# Top.net
KiCad netlist of a schematic drawn in Altium Designer
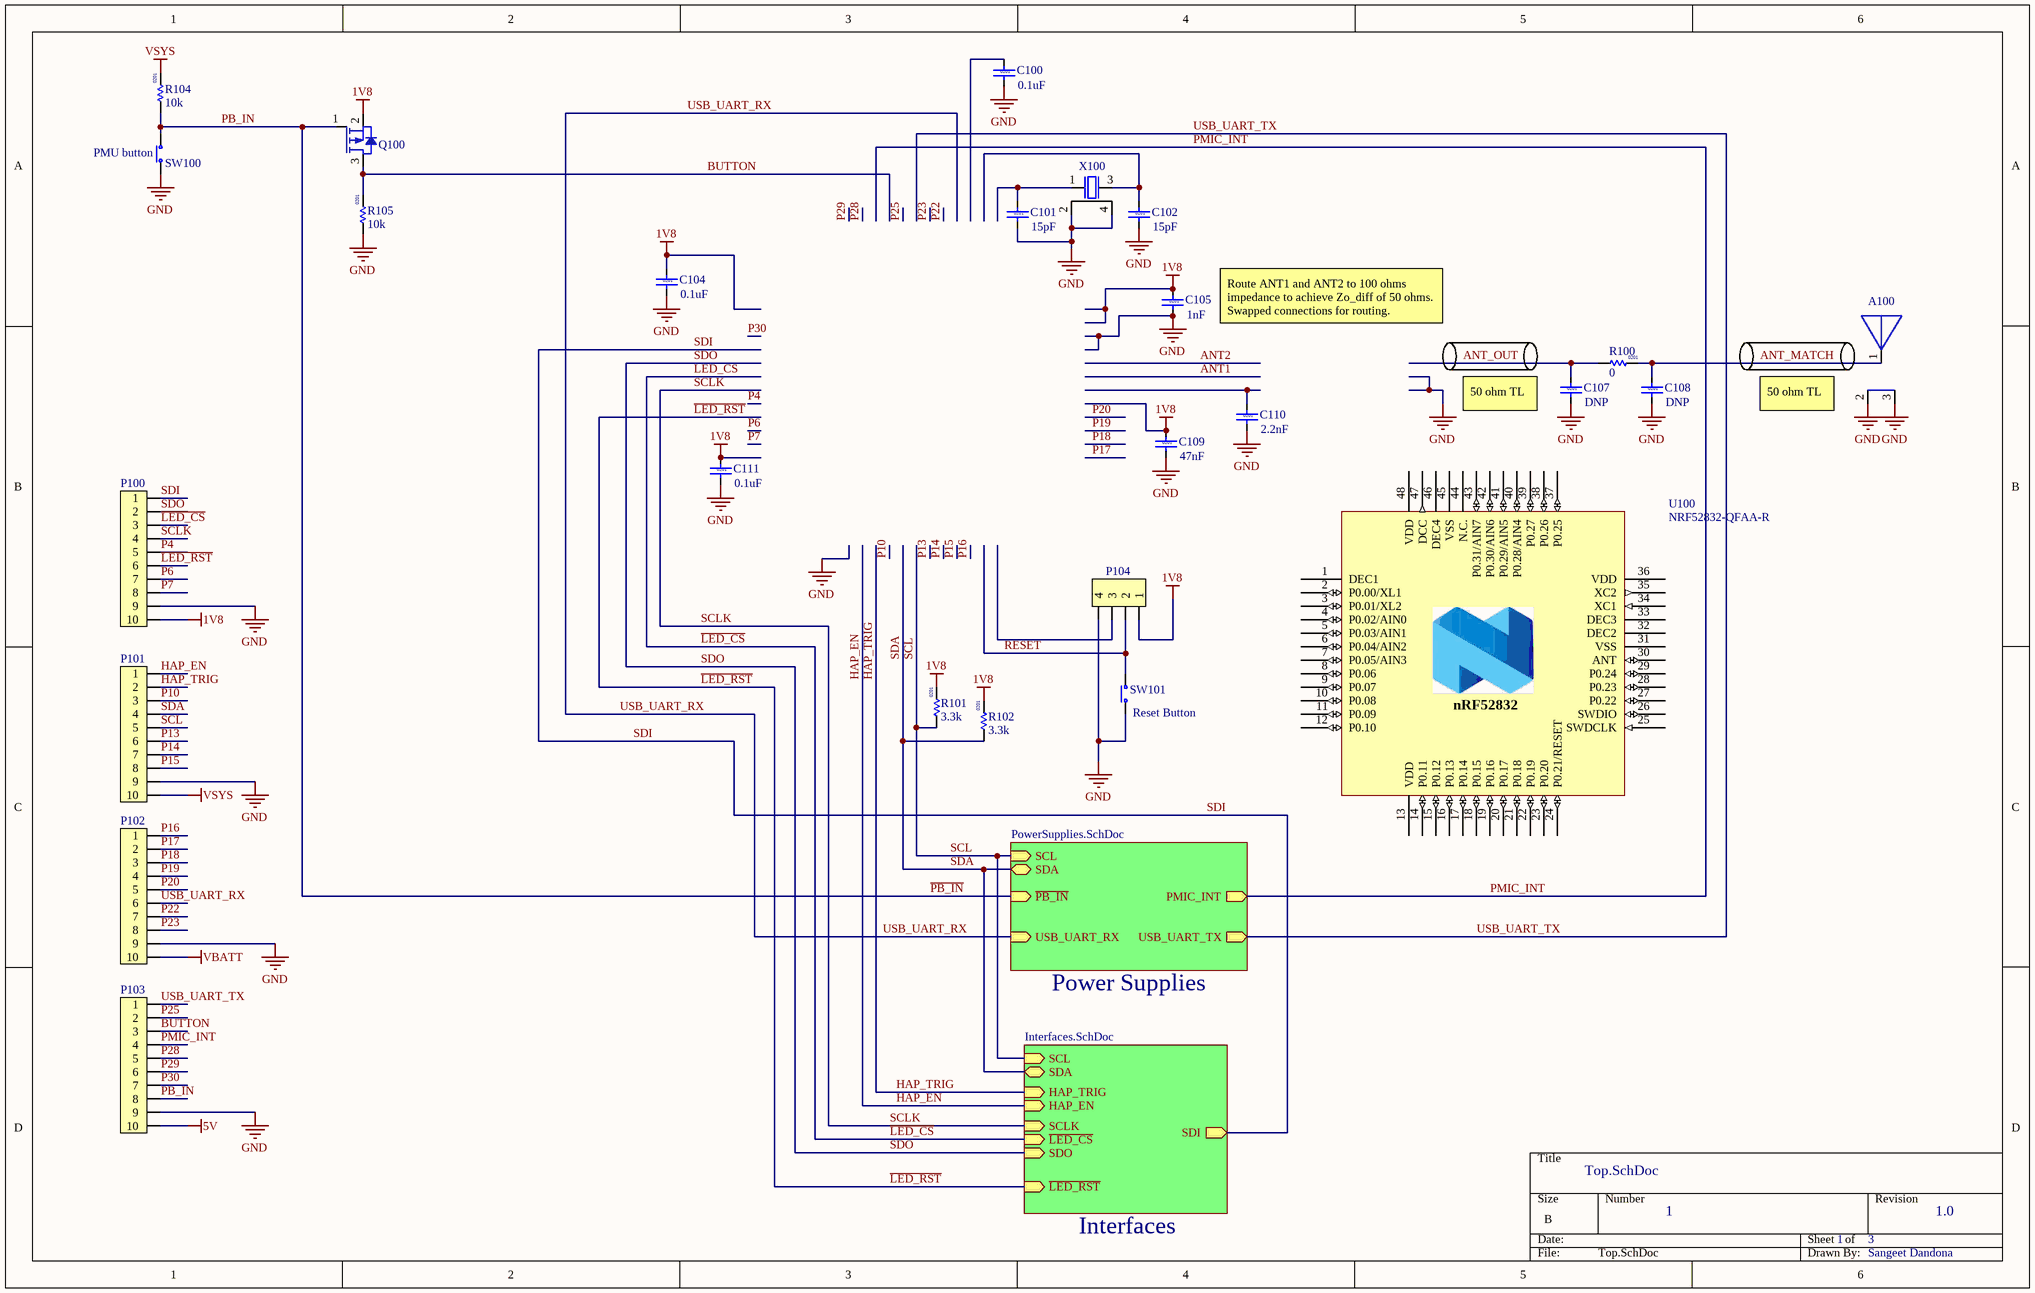
[diagram p0: Top.SchDoc]

(export (version "E")
  (design (tool "Eeschema 10.0.6"))
  (components
    (comp (ref "A100")
      (value "~")
      (footprint "2450AT07A0100")
      (description "ANTENNA SMD EIA 0402 2.4GHZ")
      (fields (field (name "MF") "Johanson Technology Inc."))
      (libsource (lib "Rigado_AltiumLib") (part "ANT_GND_4Pin"))
    )
    (comp (ref "C100")
      (value "0.1uF")
      (footprint "Cap 0201 HD")
      (description "CAP CER 0.1UF 6.3V 10% X5R 0201")
      (fields (field (name "SIZE") "0201") (field (name "MF") "Murata Electronics North America"))
      (libsource (lib "Rigado_AltiumLib") (part "Cap Chip"))
    )
    (comp (ref "C101")
      (value "15pF")
      (footprint "Cap 0201 HD")
      (description "CAP CER 15PF 25V NP0 0201")
      (fields (field (name "SIZE") "0201") (field (name "MF") "Murata Electronics North America"))
      (libsource (lib "Rigado_AltiumLib") (part "Cap Chip"))
    )
    (comp (ref "C102")
      (value "15pF")
      (footprint "Cap 0201 HD")
      (description "CAP CER 15PF 25V NP0 0201")
      (fields (field (name "SIZE") "0201") (field (name "MF") "Murata Electronics North America"))
      (libsource (lib "Rigado_AltiumLib") (part "Cap Chip"))
    )
    (comp (ref "C104")
      (value "0.1uF")
      (footprint "Cap 0201 HD")
      (description "CAP CER 0.1UF 6.3V 10% X5R 0201")
      (fields (field (name "SIZE") "0201") (field (name "MF") "Murata Electronics North America"))
      (libsource (lib "Rigado_AltiumLib") (part "Cap Chip"))
    )
    (comp (ref "C105")
      (value "1nF")
      (footprint "Cap 0201 HD")
      (description "CAP CER 1000PF 25V 10% X7R 0201")
      (fields (field (name "SIZE") "0201") (field (name "MF") "Murata Electronics North America"))
      (libsource (lib "Rigado_AltiumLib") (part "Cap Chip"))
    )
    (comp (ref "C107")
      (value "DNP")
      (footprint "Cap 0201 HD")
      (description "Capacitor, Ceramic 0201, DNP")
      (fields (field (name "SIZE") "0201"))
      (libsource (lib "Rigado_AltiumLib") (part "Cap Chip"))
    )
    (comp (ref "C108")
      (value "DNP")
      (footprint "Cap 0201 HD")
      (description "Capacitor, Ceramic 0201, DNP")
      (fields (field (name "SIZE") "0201"))
      (libsource (lib "Rigado_AltiumLib") (part "Cap Chip"))
    )
    (comp (ref "C109")
      (value "47nF")
      (footprint "Cap 0201 HD")
      (description "CAP CER 0.047UF 10V 10% X5R 0201")
      (fields (field (name "SIZE") "0201") (field (name "MF") "Taiyo Yuden"))
      (libsource (lib "Rigado_AltiumLib") (part "Cap Chip"))
    )
    (comp (ref "C110")
      (value "2.2nF")
      (footprint "Cap 0201 HD")
      (description "CAP CER 2200PF 16V 10% X7R 0201")
      (fields (field (name "SIZE") "0201") (field (name "MF") "Murata Electronics North America"))
      (libsource (lib "Rigado_AltiumLib") (part "Cap Chip"))
    )
    (comp (ref "C111")
      (value "0.1uF")
      (footprint "Cap 0201 HD")
      (description "CAP CER 0.1UF 6.3V 10% X5R 0201")
      (fields (field (name "SIZE") "0201") (field (name "MF") "Murata Electronics North America"))
      (libsource (lib "Rigado_AltiumLib") (part "Cap Chip"))
    )
    (comp (ref "P100")
      (value "~")
      (footprint "Molex 15-91-2100")
      (description "CONN HEADER 10POS .100\" VERT TIN")
      (fields (field (name "MF") "Molex, LLC"))
      (libsource (lib "JDB-001") (part "CONN-10"))
    )
    (comp (ref "P101")
      (value "~")
      (footprint "Molex 15-91-2100")
      (description "CONN HEADER 10POS .100\" VERT TIN")
      (fields (field (name "MF") "Molex, LLC"))
      (libsource (lib "JDB-001") (part "CONN-10"))
    )
    (comp (ref "P102")
      (value "~")
      (footprint "Molex 15-91-2100")
      (description "CONN HEADER 10POS .100\" VERT TIN")
      (fields (field (name "MF") "Molex, LLC"))
      (libsource (lib "JDB-001") (part "CONN-10"))
    )
    (comp (ref "P103")
      (value "~")
      (footprint "Molex 15-91-2100")
      (description "CONN HEADER 10POS .100\" VERT TIN")
      (fields (field (name "MF") "Molex, LLC"))
      (libsource (lib "JDB-001") (part "CONN-10"))
    )
    (comp (ref "P104")
      (value "~")
      (footprint "LIST_1x4_SMD")
      (description "BOARD-BOARD CONNECTOR HEADER, 4WAY, 1ROW")
      (fields (field (name "MF") "GLOBAL CONNECTOR TECHNOLOGY"))
      (libsource (lib "JDB-001") (part "CONN-4"))
    )
    (comp (ref "Q100")
      (value "~")
      (footprint "SOT-723")
      (description "MOSFET P-CH 20V 0.1A VMT3")
      (fields (field (name "MF") "Rohm Semiconductor"))
      (libsource (lib "JDB-001") (part "MOSFET-P"))
    )
    (comp (ref "R100")
      (value "0")
      (footprint "RES 0201 HD")
      (description "RES SMD 0.0OHM JUMPER 1/20W 0201")
      (fields (field (name "SIZE") "0201") (field (name "MF") "Samsung Electro-Mechanics America, Inc."))
      (libsource (lib "Rigado_AltiumLib") (part "Res sm"))
    )
    (comp (ref "R101")
      (value "3.3k")
      (footprint "RES 0201 HD")
      (description "RES SMD 3.3K OHM 5% 1/20W 0201")
      (fields (field (name "SIZE") "0201") (field (name "MF") "Samsung Electro-Mechanics America, Inc."))
      (libsource (lib "Rigado_AltiumLib") (part "Res sm"))
    )
    (comp (ref "R102")
      (value "3.3k")
      (footprint "RES 0201 HD")
      (description "RES SMD 3.3K OHM 5% 1/20W 0201")
      (fields (field (name "SIZE") "0201") (field (name "MF") "Samsung Electro-Mechanics America, Inc."))
      (libsource (lib "Rigado_AltiumLib") (part "Res sm"))
    )
    (comp (ref "R104")
      (value "10k")
      (footprint "RES 0201 HD")
      (description "RES SMD 10K OHM 5% 1/20W 0201")
      (fields (field (name "SIZE") "0201") (field (name "MF") "Rohm Semiconductor"))
      (libsource (lib "Rigado_AltiumLib") (part "Res sm"))
    )
    (comp (ref "R105")
      (value "10k")
      (footprint "RES 0201 HD")
      (description "RES SMD 10K OHM 5% 1/20W 0201")
      (fields (field (name "SIZE") "0201") (field (name "MF") "Rohm Semiconductor"))
      (libsource (lib "Rigado_AltiumLib") (part "Res sm"))
    )
    (comp (ref "SW100")
      (value "~")
      (footprint "ALPS_SKHUxxx010_WO_GND")
      (description "Tactile Switches 6.0x6.0x2.5mm 160gf")
      (fields (field (name "MF") "ALPS"))
      (libsource (lib "JDB-001") (part "SW-PB"))
    )
    (comp (ref "SW101")
      (value "~")
      (footprint "ALPS_SKHUxxx010_WO_GND")
      (description "Tactile Switches 6.0x6.0x2.5mm 160gf")
      (fields (field (name "MF") "ALPS"))
      (libsource (lib "JDB-001") (part "SW-PB"))
    )
    (comp (ref "U100")
      (value "NRF52832-QFAA-R")
      (footprint "QFN40P600X600X90-48N")
      (description "IC RF TXRX+MCU BLUETOOTH 48QFN")
      (fields (field (name "MF") "Nordic Semiconductor ASA") (field (name "MFPN") "NRF52832-QFAA-R"))
      (libsource (lib "JDB-002") (part "nRF52832_QFAA"))
    )
    (comp (ref "X100")
      (value "~")
      (footprint "XTAL_ABM11-16")
      (description "CRYSTAL 16.0000MHZ 10PF SMD")
      (fields (field (name "MF") "Abracon LLC"))
      (libsource (lib "JWB-001_Main") (part "XTAL_ABM11-16"))
    )
  )
  (nets
    (net (code "3") (name "/ANT_MATCH") (class "Default")
      (node (ref "A100") (pin "1") (pinfunction "1_1") (pintype "passive"))
      (node (ref "C108") (pin "1") (pinfunction "1_1") (pintype "passive"))
      (node (ref "R100") (pin "2") (pinfunction "2_2") (pintype "passive"))
    )
    (net (code "4") (name "/ANT_OUT") (class "Default")
      (node (ref "C107") (pin "1") (pinfunction "1_1") (pintype "passive"))
      (node (ref "R100") (pin "1") (pinfunction "1_1") (pintype "passive"))
    )
    (net (code "5") (name "/BUTTON") (class "Default")
      (node (ref "P103") (pin "3") (pinfunction "3_3") (pintype "power_in"))
      (node (ref "Q100") (pin "3") (pinfunction "D_3") (pintype "passive"))
      (node (ref "R105") (pin "2") (pinfunction "2_2") (pintype "passive"))
    )
    (net (code "6") (name "/HAP_EN") (class "Default")
      (node (ref "P101") (pin "1") (pinfunction "1_1") (pintype "power_in"))
    )
    (net (code "7") (name "/HAP_TRIG") (class "Default")
      (node (ref "P101") (pin "2") (pinfunction "2_2") (pintype "power_in"))
    )
    (net (code "8") (name "/LED_CS") (class "Default")
      (node (ref "P100") (pin "3") (pinfunction "3_3") (pintype "power_in"))
    )
    (net (code "9") (name "/LED_RST") (class "Default")
      (node (ref "P100") (pin "6") (pinfunction "6_6") (pintype "power_in"))
    )
    (net (code "10") (name "/P4") (class "Default")
      (node (ref "P100") (pin "5") (pinfunction "5_5") (pintype "power_in"))
    )
    (net (code "11") (name "/P6") (class "Default")
      (node (ref "P100") (pin "7") (pinfunction "7_7") (pintype "power_in"))
    )
    (net (code "12") (name "/P7") (class "Default")
      (node (ref "P100") (pin "8") (pinfunction "8_8") (pintype "power_in"))
    )
    (net (code "13") (name "/P10") (class "Default")
      (node (ref "P101") (pin "3") (pinfunction "3_3") (pintype "power_in"))
    )
    (net (code "14") (name "/P13") (class "Default")
      (node (ref "P101") (pin "6") (pinfunction "6_6") (pintype "power_in"))
    )
    (net (code "15") (name "/P14") (class "Default")
      (node (ref "P101") (pin "7") (pinfunction "7_7") (pintype "power_in"))
    )
    (net (code "16") (name "/P15") (class "Default")
      (node (ref "P101") (pin "8") (pinfunction "8_8") (pintype "power_in"))
    )
    (net (code "17") (name "/P16") (class "Default")
      (node (ref "P102") (pin "1") (pinfunction "1_1") (pintype "power_in"))
    )
    (net (code "18") (name "/P17") (class "Default")
      (node (ref "P102") (pin "2") (pinfunction "2_2") (pintype "power_in"))
    )
    (net (code "19") (name "/P18") (class "Default")
      (node (ref "P102") (pin "3") (pinfunction "3_3") (pintype "power_in"))
    )
    (net (code "20") (name "/P19") (class "Default")
      (node (ref "P102") (pin "4") (pinfunction "4_4") (pintype "power_in"))
    )
    (net (code "21") (name "/P20") (class "Default")
      (node (ref "P102") (pin "5") (pinfunction "5_5") (pintype "power_in"))
    )
    (net (code "22") (name "/P22") (class "Default")
      (node (ref "P102") (pin "7") (pinfunction "7_7") (pintype "power_in"))
    )
    (net (code "23") (name "/P23") (class "Default")
      (node (ref "P102") (pin "8") (pinfunction "8_8") (pintype "power_in"))
    )
    (net (code "24") (name "/P25") (class "Default")
      (node (ref "P103") (pin "2") (pinfunction "2_2") (pintype "power_in"))
    )
    (net (code "25") (name "/P28") (class "Default")
      (node (ref "P103") (pin "5") (pinfunction "5_5") (pintype "power_in"))
    )
    (net (code "26") (name "/P29") (class "Default")
      (node (ref "P103") (pin "6") (pinfunction "6_6") (pintype "power_in"))
    )
    (net (code "27") (name "/P30") (class "Default")
      (node (ref "P103") (pin "7") (pinfunction "7_7") (pintype "power_in"))
    )
    (net (code "28") (name "/PB_IN") (class "Default")
      (node (ref "P103") (pin "8") (pinfunction "8_8") (pintype "power_in"))
      (node (ref "Q100") (pin "1") (pinfunction "G_1") (pintype "passive"))
      (node (ref "R104") (pin "1") (pinfunction "1_1") (pintype "passive"))
      (node (ref "SW100") (pin "1") (pinfunction "N.O_1") (pintype "passive"))
    )
    (net (code "29") (name "/PMIC_INT") (class "Default")
      (node (ref "P103") (pin "4") (pinfunction "4_4") (pintype "power_in"))
    )
    (net (code "30") (name "/RESET") (class "Default")
      (node (ref "P104") (pin "2") (pinfunction "2_2") (pintype "passive"))
      (node (ref "SW101") (pin "1") (pinfunction "N.O_1") (pintype "passive"))
    )
    (net (code "31") (name "/SCL") (class "Default")
      (node (ref "P101") (pin "5") (pinfunction "5_5") (pintype "power_in"))
      (node (ref "R101") (pin "1") (pinfunction "1_1") (pintype "passive"))
    )
    (net (code "32") (name "/SCLK") (class "Default")
      (node (ref "P100") (pin "4") (pinfunction "4_4") (pintype "power_in"))
    )
    (net (code "33") (name "/SDA") (class "Default")
      (node (ref "P101") (pin "4") (pinfunction "4_4") (pintype "power_in"))
      (node (ref "R102") (pin "1") (pinfunction "1_1") (pintype "passive"))
    )
    (net (code "34") (name "/SDI") (class "Default")
      (node (ref "P100") (pin "1") (pinfunction "1_1") (pintype "power_in"))
    )
    (net (code "35") (name "/SDO") (class "Default")
      (node (ref "P100") (pin "2") (pinfunction "2_2") (pintype "power_in"))
    )
    (net (code "36") (name "/USB_UART_RX") (class "Default")
      (node (ref "P102") (pin "6") (pinfunction "6_6") (pintype "power_in"))
    )
    (net (code "37") (name "/USB_UART_TX") (class "Default")
      (node (ref "P103") (pin "1") (pinfunction "1_1") (pintype "power_in"))
    )
    (net (code "38") (name "1V8") (class "Default")
      (node (ref "C104") (pin "1") (pinfunction "1_1") (pintype "passive"))
      (node (ref "C105") (pin "1") (pinfunction "1_1") (pintype "passive"))
      (node (ref "C109") (pin "1") (pinfunction "1_1") (pintype "passive"))
      (node (ref "C111") (pin "1") (pinfunction "1_1") (pintype "passive"))
      (node (ref "P100") (pin "10") (pinfunction "10_10") (pintype "power_in"))
      (node (ref "P104") (pin "1") (pinfunction "1_1") (pintype "passive"))
      (node (ref "Q100") (pin "2") (pinfunction "S_2") (pintype "passive"))
      (node (ref "R101") (pin "2") (pinfunction "2_2") (pintype "passive"))
      (node (ref "R102") (pin "2") (pinfunction "2_2") (pintype "passive"))
    )
    (net (code "39") (name "5V") (class "Default")
      (node (ref "P103") (pin "10") (pinfunction "10_10") (pintype "power_in"))
    )
    (net (code "40") (name "GND") (class "Default")
      (node (ref "A100") (pin "2") (pinfunction "2_2") (pintype "power_in"))
      (node (ref "A100") (pin "3") (pinfunction "3_3") (pintype "power_in"))
      (node (ref "C100") (pin "2") (pinfunction "2_2") (pintype "passive"))
      (node (ref "C101") (pin "2") (pinfunction "2_2") (pintype "passive"))
      (node (ref "C102") (pin "2") (pinfunction "2_2") (pintype "passive"))
      (node (ref "C104") (pin "2") (pinfunction "2_2") (pintype "passive"))
      (node (ref "C105") (pin "2") (pinfunction "2_2") (pintype "passive"))
      (node (ref "C107") (pin "2") (pinfunction "2_2") (pintype "passive"))
      (node (ref "C108") (pin "2") (pinfunction "2_2") (pintype "passive"))
      (node (ref "C109") (pin "2") (pinfunction "2_2") (pintype "passive"))
      (node (ref "C110") (pin "2") (pinfunction "2_2") (pintype "passive"))
      (node (ref "C111") (pin "2") (pinfunction "2_2") (pintype "passive"))
      (node (ref "P100") (pin "9") (pinfunction "9_9") (pintype "power_in"))
      (node (ref "P101") (pin "9") (pinfunction "9_9") (pintype "power_in"))
      (node (ref "P102") (pin "9") (pinfunction "9_9") (pintype "power_in"))
      (node (ref "P103") (pin "9") (pinfunction "9_9") (pintype "power_in"))
      (node (ref "P104") (pin "4") (pinfunction "4_4") (pintype "power_in"))
      (node (ref "R105") (pin "1") (pinfunction "1_1") (pintype "passive"))
      (node (ref "SW100") (pin "2") (pinfunction "COM_2") (pintype "passive"))
      (node (ref "SW101") (pin "2") (pinfunction "COM_2") (pintype "passive"))
      (node (ref "U100") (pin "49") (pinfunction "GND_49") (pintype "power_in"))
      (node (ref "X100") (pin "2") (pintype "passive"))
      (node (ref "X100") (pin "4") (pintype "passive"))
    )
    (net (code "41") (name "Net-(C101-Pad1)") (class "Default")
      (node (ref "C101") (pin "1") (pinfunction "1_1") (pintype "passive"))
      (node (ref "X100") (pin "1") (pintype "passive"))
    )
    (net (code "42") (name "Net-(C102-Pad1)") (class "Default")
      (node (ref "C102") (pin "1") (pinfunction "1_1") (pintype "passive"))
      (node (ref "X100") (pin "3") (pintype "passive"))
    )
    (net (code "43") (name "VBATT") (class "Default")
      (node (ref "P102") (pin "10") (pinfunction "10_10") (pintype "power_in"))
    )
    (net (code "44") (name "VSYS") (class "Default")
      (node (ref "P101") (pin "10") (pinfunction "10_10") (pintype "power_in"))
      (node (ref "R104") (pin "2") (pinfunction "2_2") (pintype "passive"))
    )
    (net (code "45") (name "unconnected-(C100-Pad1)") (class "Default")
      (node (ref "C100") (pin "1") (pinfunction "1_1") (pintype "passive"))
    )
    (net (code "46") (name "unconnected-(C110-Pad1)") (class "Default")
      (node (ref "C110") (pin "1") (pinfunction "1_1") (pintype "passive"))
    )
    (net (code "47") (name "unconnected-(P104-Pad3)") (class "Default")
      (node (ref "P104") (pin "3") (pinfunction "3_3") (pintype "power_in"))
    )
    (net (code "48") (name "unconnected-(U100-ANT-Pad30)") (class "Default")
      (node (ref "U100") (pin "30") (pinfunction "ANT_30") (pintype "bidirectional"))
    )
    (net (code "49") (name "unconnected-(U100-DCC-Pad47)") (class "Default")
      (node (ref "U100") (pin "47") (pinfunction "DCC_47") (pintype "output"))
    )
    (net (code "50") (name "unconnected-(U100-DEC1-Pad1)") (class "Default")
      (node (ref "U100") (pin "1") (pinfunction "DEC1_1") (pintype "power_in"))
    )
    (net (code "51") (name "unconnected-(U100-DEC2-Pad32)") (class "Default")
      (node (ref "U100") (pin "32") (pinfunction "DEC2_32") (pintype "power_in"))
    )
    (net (code "52") (name "unconnected-(U100-DEC3-Pad33)") (class "Default")
      (node (ref "U100") (pin "33") (pinfunction "DEC3_33") (pintype "power_in"))
    )
    (net (code "53") (name "unconnected-(U100-DEC4-Pad46)") (class "Default")
      (node (ref "U100") (pin "46") (pinfunction "DEC4_46") (pintype "power_in"))
    )
    (net (code "54") (name "unconnected-(U100-N.C.-Pad44)") (class "Default")
      (node (ref "U100") (pin "44") (pinfunction "N.C._44") (pintype "power_in"))
    )
    (net (code "55") (name "unconnected-(U100-P0.00{slash}XL1-Pad2)") (class "Default")
      (node (ref "U100") (pin "2") (pinfunction "P0.00/XL1_2") (pintype "bidirectional"))
    )
    (net (code "56") (name "unconnected-(U100-P0.01{slash}XL2-Pad3)") (class "Default")
      (node (ref "U100") (pin "3") (pinfunction "P0.01/XL2_3") (pintype "bidirectional"))
    )
    (net (code "57") (name "unconnected-(U100-P0.02{slash}AIN0-Pad4)") (class "Default")
      (node (ref "U100") (pin "4") (pinfunction "P0.02/AIN0_4") (pintype "bidirectional"))
    )
    (net (code "58") (name "unconnected-(U100-P0.03{slash}AIN1-Pad5)") (class "Default")
      (node (ref "U100") (pin "5") (pinfunction "P0.03/AIN1_5") (pintype "bidirectional"))
    )
    (net (code "59") (name "unconnected-(U100-P0.04{slash}AIN2-Pad6)") (class "Default")
      (node (ref "U100") (pin "6") (pinfunction "P0.04/AIN2_6") (pintype "bidirectional"))
    )
    (net (code "60") (name "unconnected-(U100-P0.05{slash}AIN3-Pad7)") (class "Default")
      (node (ref "U100") (pin "7") (pinfunction "P0.05/AIN3_7") (pintype "bidirectional"))
    )
    (net (code "61") (name "unconnected-(U100-P0.06-Pad8)") (class "Default")
      (node (ref "U100") (pin "8") (pinfunction "P0.06_8") (pintype "bidirectional"))
    )
    (net (code "62") (name "unconnected-(U100-P0.07-Pad9)") (class "Default")
      (node (ref "U100") (pin "9") (pinfunction "P0.07_9") (pintype "bidirectional"))
    )
    (net (code "63") (name "unconnected-(U100-P0.08-Pad10)") (class "Default")
      (node (ref "U100") (pin "10") (pinfunction "P0.08_10") (pintype "bidirectional"))
    )
    (net (code "64") (name "unconnected-(U100-P0.09-Pad11)") (class "Default")
      (node (ref "U100") (pin "11") (pinfunction "P0.09_11") (pintype "bidirectional"))
    )
    (net (code "65") (name "unconnected-(U100-P0.10-Pad12)") (class "Default")
      (node (ref "U100") (pin "12") (pinfunction "P0.10_12") (pintype "bidirectional"))
    )
    (net (code "66") (name "unconnected-(U100-P0.11-Pad14)") (class "Default")
      (node (ref "U100") (pin "14") (pinfunction "P0.11_14") (pintype "bidirectional"))
    )
    (net (code "67") (name "unconnected-(U100-P0.12-Pad15)") (class "Default")
      (node (ref "U100") (pin "15") (pinfunction "P0.12_15") (pintype "bidirectional"))
    )
    (net (code "68") (name "unconnected-(U100-P0.13-Pad16)") (class "Default")
      (node (ref "U100") (pin "16") (pinfunction "P0.13_16") (pintype "bidirectional"))
    )
    (net (code "69") (name "unconnected-(U100-P0.14-Pad17)") (class "Default")
      (node (ref "U100") (pin "17") (pinfunction "P0.14_17") (pintype "bidirectional"))
    )
    (net (code "70") (name "unconnected-(U100-P0.15-Pad18)") (class "Default")
      (node (ref "U100") (pin "18") (pinfunction "P0.15_18") (pintype "bidirectional"))
    )
    (net (code "71") (name "unconnected-(U100-P0.16-Pad19)") (class "Default")
      (node (ref "U100") (pin "19") (pinfunction "P0.16_19") (pintype "bidirectional"))
    )
    (net (code "72") (name "unconnected-(U100-P0.17-Pad20)") (class "Default")
      (node (ref "U100") (pin "20") (pinfunction "P0.17_20") (pintype "bidirectional"))
    )
    (net (code "73") (name "unconnected-(U100-P0.18-Pad21)") (class "Default")
      (node (ref "U100") (pin "21") (pinfunction "P0.18_21") (pintype "bidirectional"))
    )
    (net (code "74") (name "unconnected-(U100-P0.19-Pad22)") (class "Default")
      (node (ref "U100") (pin "22") (pinfunction "P0.19_22") (pintype "bidirectional"))
    )
    (net (code "75") (name "unconnected-(U100-P0.20-Pad23)") (class "Default")
      (node (ref "U100") (pin "23") (pinfunction "P0.20_23") (pintype "bidirectional"))
    )
    (net (code "76") (name "unconnected-(U100-P0.21{slash}RESET-Pad24)") (class "Default")
      (node (ref "U100") (pin "24") (pinfunction "P0.21/RESET_24") (pintype "bidirectional"))
    )
    (net (code "77") (name "unconnected-(U100-P0.22-Pad27)") (class "Default")
      (node (ref "U100") (pin "27") (pinfunction "P0.22_27") (pintype "bidirectional"))
    )
    (net (code "78") (name "unconnected-(U100-P0.23-Pad28)") (class "Default")
      (node (ref "U100") (pin "28") (pinfunction "P0.23_28") (pintype "bidirectional"))
    )
    (net (code "79") (name "unconnected-(U100-P0.24-Pad29)") (class "Default")
      (node (ref "U100") (pin "29") (pinfunction "P0.24_29") (pintype "bidirectional"))
    )
    (net (code "80") (name "unconnected-(U100-P0.25-Pad37)") (class "Default")
      (node (ref "U100") (pin "37") (pinfunction "P0.25_37") (pintype "bidirectional"))
    )
    (net (code "81") (name "unconnected-(U100-P0.26-Pad38)") (class "Default")
      (node (ref "U100") (pin "38") (pinfunction "P0.26_38") (pintype "bidirectional"))
    )
    (net (code "82") (name "unconnected-(U100-P0.27-Pad39)") (class "Default")
      (node (ref "U100") (pin "39") (pinfunction "P0.27_39") (pintype "bidirectional"))
    )
    (net (code "83") (name "unconnected-(U100-P0.28{slash}AIN4-Pad40)") (class "Default")
      (node (ref "U100") (pin "40") (pinfunction "P0.28/AIN4_40") (pintype "bidirectional"))
    )
    (net (code "84") (name "unconnected-(U100-P0.29{slash}AIN5-Pad41)") (class "Default")
      (node (ref "U100") (pin "41") (pinfunction "P0.29/AIN5_41") (pintype "bidirectional"))
    )
    (net (code "85") (name "unconnected-(U100-P0.30{slash}AIN6-Pad42)") (class "Default")
      (node (ref "U100") (pin "42") (pinfunction "P0.30/AIN6_42") (pintype "bidirectional"))
    )
    (net (code "86") (name "unconnected-(U100-P0.31{slash}AIN7-Pad43)") (class "Default")
      (node (ref "U100") (pin "43") (pinfunction "P0.31/AIN7_43") (pintype "bidirectional"))
    )
    (net (code "87") (name "unconnected-(U100-SWDCLK-Pad25)") (class "Default")
      (node (ref "U100") (pin "25") (pinfunction "SWDCLK_25") (pintype "input"))
    )
    (net (code "88") (name "unconnected-(U100-SWDIO-Pad26)") (class "Default")
      (node (ref "U100") (pin "26") (pinfunction "SWDIO_26") (pintype "bidirectional"))
    )
    (net (code "89") (name "unconnected-(U100-VDD-Pad13)") (class "Default")
      (node (ref "U100") (pin "13") (pinfunction "VDD_13") (pintype "power_in"))
    )
    (net (code "90") (name "unconnected-(U100-VDD-Pad36)") (class "Default")
      (node (ref "U100") (pin "36") (pinfunction "VDD_36") (pintype "power_in"))
    )
    (net (code "91") (name "unconnected-(U100-VDD-Pad48)") (class "Default")
      (node (ref "U100") (pin "48") (pinfunction "VDD_48") (pintype "power_in"))
    )
    (net (code "92") (name "unconnected-(U100-VSS-Pad31)") (class "Default")
      (node (ref "U100") (pin "31") (pinfunction "VSS_31") (pintype "power_in"))
    )
    (net (code "93") (name "unconnected-(U100-VSS-Pad45)") (class "Default")
      (node (ref "U100") (pin "45") (pinfunction "VSS_45") (pintype "power_in"))
    )
    (net (code "94") (name "unconnected-(U100-XC1-Pad34)") (class "Default")
      (node (ref "U100") (pin "34") (pinfunction "XC1_34") (pintype "input"))
    )
    (net (code "95") (name "unconnected-(U100-XC2-Pad35)") (class "Default")
      (node (ref "U100") (pin "35") (pinfunction "XC2_35") (pintype "output"))
    )
  )
)
